# 23_LMS2_RX1_BB_ADC.net
KiCad netlist of a schematic drawn in Altium Designer
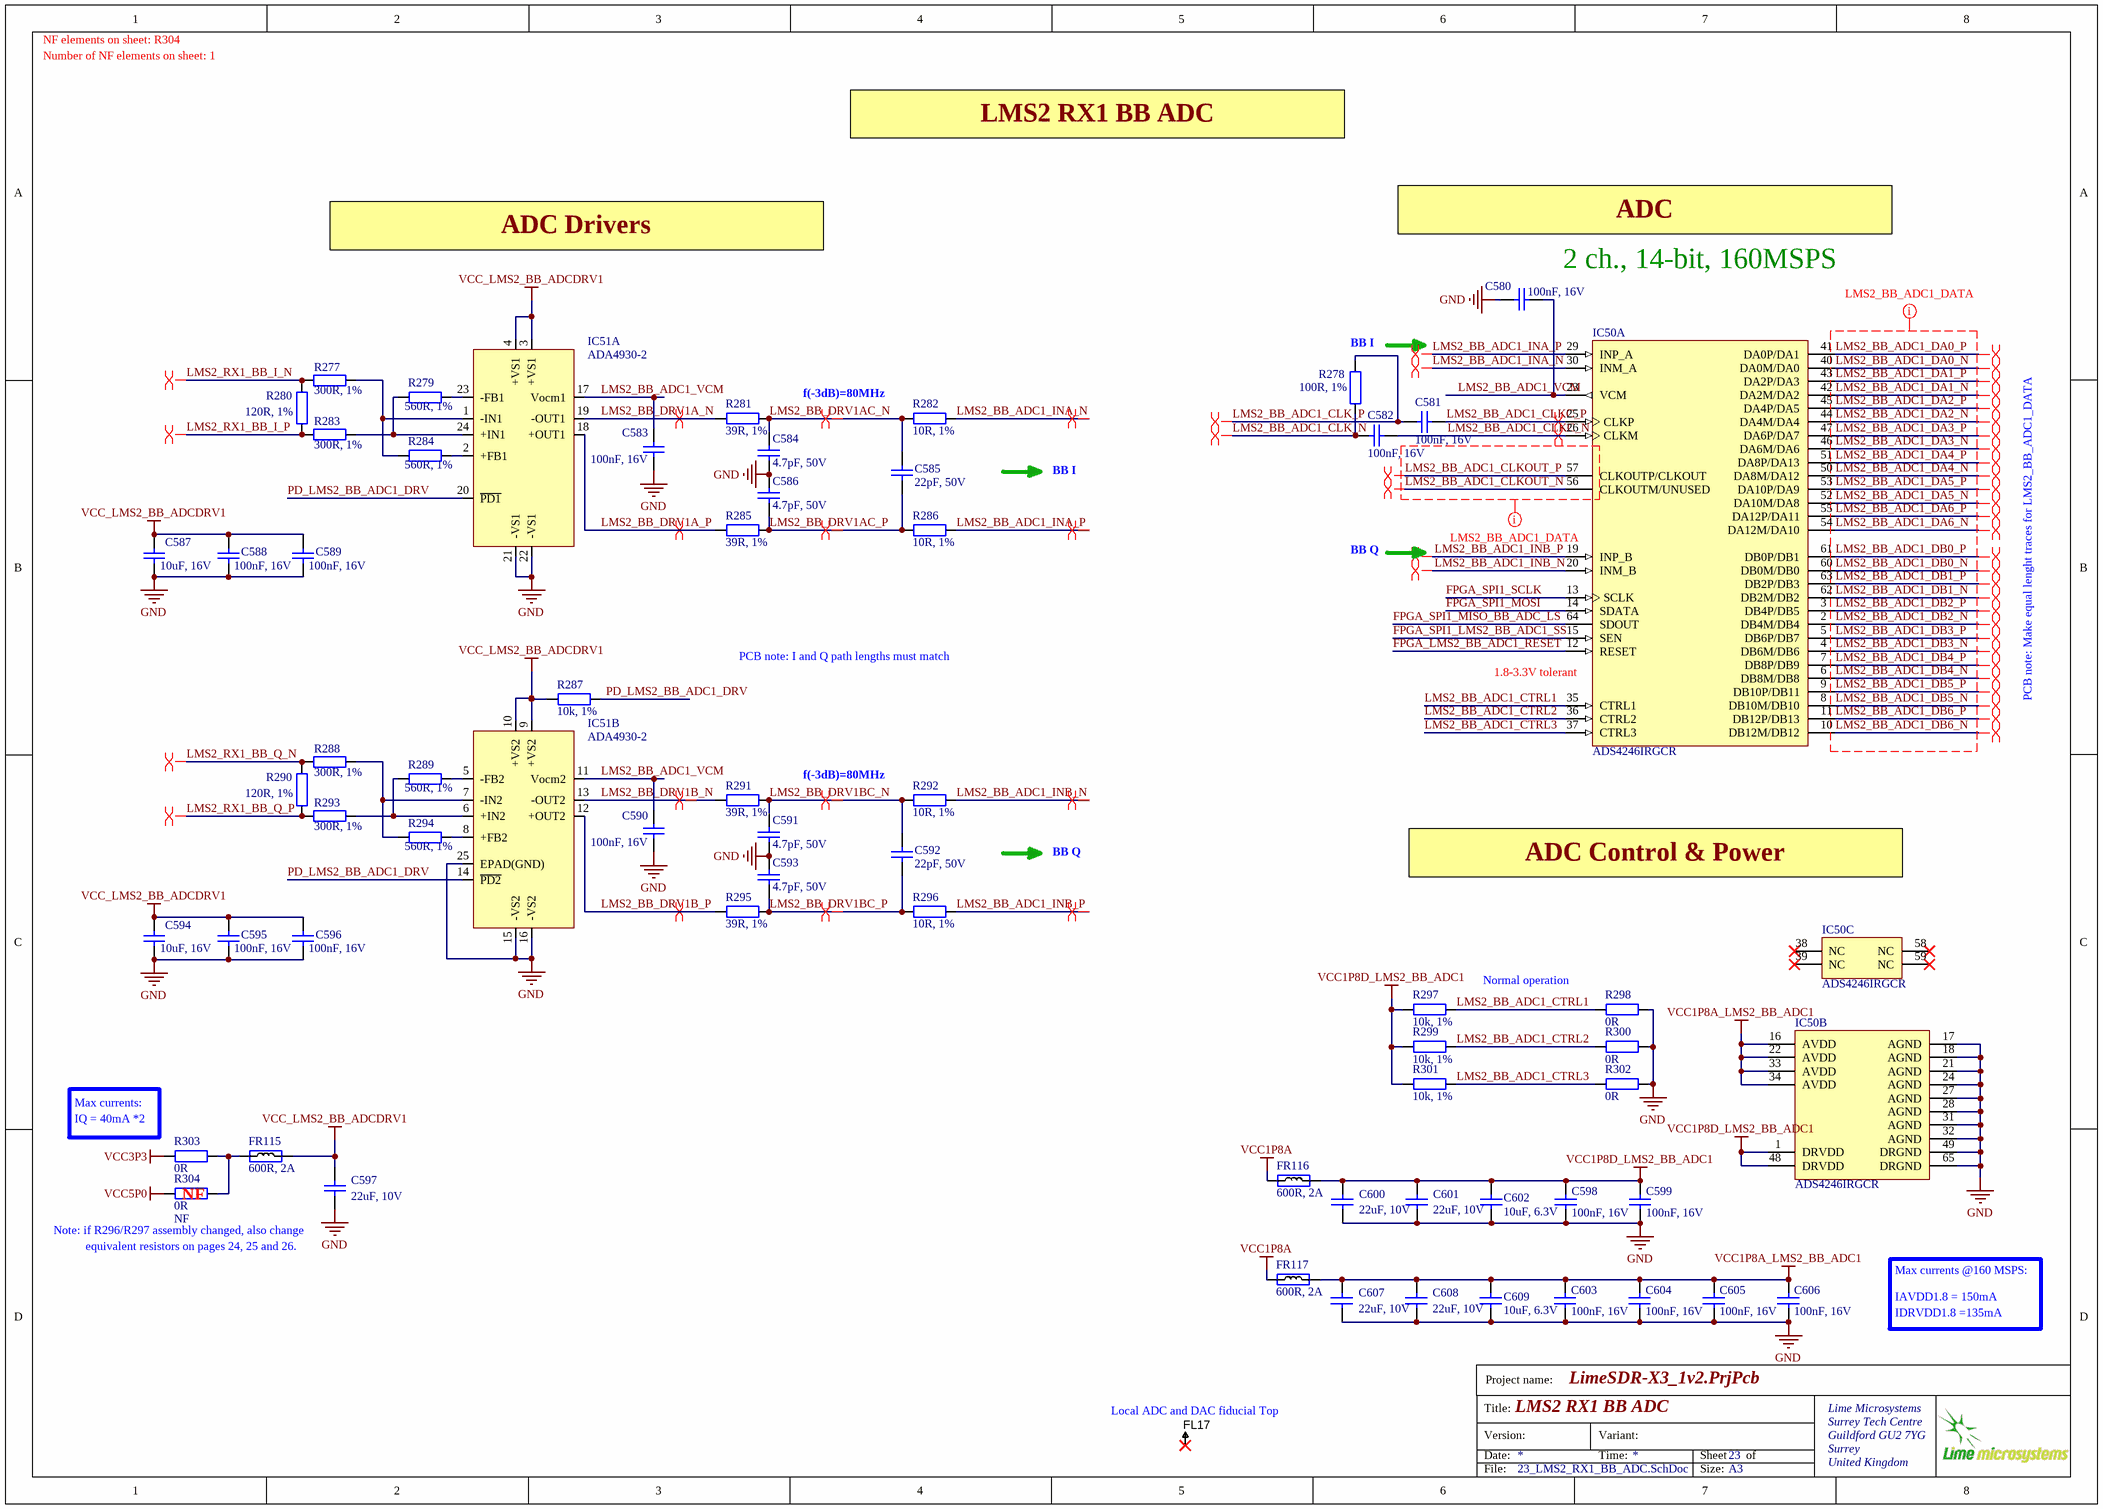
[diagram p0: 23_LMS2_RX1_BB_ADC.SchDoc]

(export (version "E")
  (design (tool "Eeschema 10.0.6"))
  (components
    (comp (ref "C580")
      (value "100nF, 16V")
      (footprint "CAP0402")
      (fields (field (name "TOLERANCE") "10 %") (field (name "MANUFACTURER") "Murata Electronics"))
      (libsource (lib "") (part "Cap_0603_1"))
    )
    (comp (ref "C581")
      (value "100nF, 16V")
      (footprint "CAP0402")
      (fields (field (name "TOLERANCE") "10 %") (field (name "MANUFACTURER") "Murata Electronics"))
      (libsource (lib "") (part "Cap_0603_1"))
    )
    (comp (ref "C582")
      (value "100nF, 16V")
      (footprint "CAP0402")
      (fields (field (name "TOLERANCE") "10 %") (field (name "MANUFACTURER") "Murata Electronics"))
      (libsource (lib "") (part "Cap_0603_2"))
    )
    (comp (ref "C583")
      (value "100nF, 16V")
      (footprint "CAP0402")
      (fields (field (name "TOLERANCE") "10 %") (field (name "MANUFACTURER") "Murata Electronics"))
      (libsource (lib "") (part "Cap_0603_2"))
    )
    (comp (ref "C584")
      (value "4.7pF, 50V")
      (footprint "CAP0402")
      (fields (field (name "MANUFACTURER") "MURATA"))
      (libsource (lib "LimeMicroAltiumLib_schLib") (part "Cap_0402"))
    )
    (comp (ref "C585")
      (value "22pF, 50V")
      (footprint "CAP0402")
      (fields (field (name "TOLERANCE") "±5%") (field (name "MANUFACTURER") "Yageo"))
      (libsource (lib "") (part "Cap_0402_1"))
    )
    (comp (ref "C586")
      (value "4.7pF, 50V")
      (footprint "CAP0402")
      (fields (field (name "MANUFACTURER") "MURATA"))
      (libsource (lib "LimeMicroAltiumLib_schLib") (part "Cap_0402"))
    )
    (comp (ref "C587")
      (value "10uF, 16V")
      (footprint "CAP0603")
      (fields (field (name "MANUFACTURER") "Yageo") (field (name "TOLERANCE") "±20%"))
      (libsource (lib "LimeMicroAltiumLib_schLib") (part "Cap_0603"))
    )
    (comp (ref "C588")
      (value "100nF, 16V")
      (footprint "CAP0402")
      (fields (field (name "TOLERANCE") "10 %") (field (name "MANUFACTURER") "Murata Electronics"))
      (libsource (lib "") (part "Cap_0603_2"))
    )
    (comp (ref "C589")
      (value "100nF, 16V")
      (footprint "CAP0402")
      (fields (field (name "TOLERANCE") "10 %") (field (name "MANUFACTURER") "Murata Electronics"))
      (libsource (lib "") (part "Cap_0603_2"))
    )
    (comp (ref "C590")
      (value "100nF, 16V")
      (footprint "CAP0402")
      (fields (field (name "TOLERANCE") "10 %") (field (name "MANUFACTURER") "Murata Electronics"))
      (libsource (lib "") (part "Cap_0603_5"))
    )
    (comp (ref "C591")
      (value "4.7pF, 50V")
      (footprint "CAP0402")
      (fields (field (name "MANUFACTURER") "MURATA"))
      (libsource (lib "LimeMicroAltiumLib_schLib") (part "Cap_0402"))
    )
    (comp (ref "C592")
      (value "22pF, 50V")
      (footprint "CAP0402")
      (fields (field (name "TOLERANCE") "±5%") (field (name "MANUFACTURER") "Yageo"))
      (libsource (lib "") (part "Cap_0402_1"))
    )
    (comp (ref "C593")
      (value "4.7pF, 50V")
      (footprint "CAP0402")
      (fields (field (name "MANUFACTURER") "MURATA"))
      (libsource (lib "LimeMicroAltiumLib_schLib") (part "Cap_0402"))
    )
    (comp (ref "C594")
      (value "10uF, 16V")
      (footprint "CAP0603")
      (fields (field (name "MANUFACTURER") "Yageo") (field (name "TOLERANCE") "±20%"))
      (libsource (lib "LimeMicroAltiumLib_schLib") (part "Cap_0603"))
    )
    (comp (ref "C595")
      (value "100nF, 16V")
      (footprint "CAP0402")
      (fields (field (name "TOLERANCE") "10 %") (field (name "MANUFACTURER") "Murata Electronics"))
      (libsource (lib "") (part "Cap_0603_2"))
    )
    (comp (ref "C596")
      (value "100nF, 16V")
      (footprint "CAP0402")
      (fields (field (name "TOLERANCE") "10 %") (field (name "MANUFACTURER") "Murata Electronics"))
      (libsource (lib "") (part "Cap_0603_2"))
    )
    (comp (ref "C597")
      (value "22uF, 10V")
      (footprint "CAP0603")
      (fields (field (name "TOLERANCE") "20 %") (field (name "MANUFACTURER") "TDK Corporation"))
      (libsource (lib "") (part "Cap_0603_4"))
    )
    (comp (ref "C598")
      (value "100nF, 16V")
      (footprint "CAP0402")
      (fields (field (name "TOLERANCE") "10 %") (field (name "MANUFACTURER") "Murata Electronics"))
      (libsource (lib "") (part "Cap_0603_3"))
    )
    (comp (ref "C599")
      (value "100nF, 16V")
      (footprint "CAP0402")
      (fields (field (name "TOLERANCE") "10 %") (field (name "MANUFACTURER") "Murata Electronics"))
      (libsource (lib "") (part "Cap_0603_3"))
    )
    (comp (ref "C600")
      (value "22uF, 10V")
      (footprint "CAP0603")
      (fields (field (name "TOLERANCE") "20 %") (field (name "MANUFACTURER") "TDK Corporation"))
      (libsource (lib "") (part "Cap_0603_3"))
    )
    (comp (ref "C601")
      (value "22uF, 10V")
      (footprint "CAP0603")
      (fields (field (name "TOLERANCE") "20 %") (field (name "MANUFACTURER") "TDK Corporation"))
      (libsource (lib "") (part "Cap_0603_3"))
    )
    (comp (ref "C602")
      (value "10uF, 6.3V")
      (footprint "CAP0603")
      (fields (field (name "TOLERANCE") "±20%") (field (name "MANUFACTURER") "Yageo"))
      (libsource (lib "") (part "Cap_0603_6"))
    )
    (comp (ref "C603")
      (value "100nF, 16V")
      (footprint "CAP0402")
      (fields (field (name "TOLERANCE") "10 %") (field (name "MANUFACTURER") "Murata Electronics"))
      (libsource (lib "LimeFPGAboard_schLib") (part "Cap_0603"))
    )
    (comp (ref "C604")
      (value "100nF, 16V")
      (footprint "CAP0402")
      (fields (field (name "TOLERANCE") "10 %") (field (name "MANUFACTURER") "Murata Electronics"))
      (libsource (lib "LimeFPGAboard_schLib") (part "Cap_0603"))
    )
    (comp (ref "C605")
      (value "100nF, 16V")
      (footprint "CAP0402")
      (fields (field (name "TOLERANCE") "10 %") (field (name "MANUFACTURER") "Murata Electronics"))
      (libsource (lib "LimeFPGAboard_schLib") (part "Cap_0603"))
    )
    (comp (ref "C606")
      (value "100nF, 16V")
      (footprint "CAP0402")
      (fields (field (name "TOLERANCE") "10 %") (field (name "MANUFACTURER") "Murata Electronics"))
      (libsource (lib "LimeFPGAboard_schLib") (part "Cap_0603"))
    )
    (comp (ref "C607")
      (value "22uF, 10V")
      (footprint "CAP0603")
      (fields (field (name "TOLERANCE") "20 %") (field (name "MANUFACTURER") "TDK Corporation"))
      (libsource (lib "LimeFPGAboard_schLib") (part "Cap_0603"))
    )
    (comp (ref "C608")
      (value "22uF, 10V")
      (footprint "CAP0603")
      (fields (field (name "TOLERANCE") "20 %") (field (name "MANUFACTURER") "TDK Corporation"))
      (libsource (lib "LimeFPGAboard_schLib") (part "Cap_0603"))
    )
    (comp (ref "C609")
      (value "10uF, 6.3V")
      (footprint "CAP0603")
      (fields (field (name "TOLERANCE") "±20%") (field (name "MANUFACTURER") "Yageo"))
      (libsource (lib "") (part "Cap_0603_7"))
    )
    (comp (ref "FL17")
      (value "Fiducial")
      (footprint "Fiducial_local")
      (libsource (lib "LimeMicroAltiumLib_schLib") (part "Fiducial"))
    )
    (comp (ref "FR115")
      (value "600R, 2A")
      (footprint "RES0805")
      (fields (field (name "MANUFACTURER") "TDK Corporation"))
      (libsource (lib "LimeMicroAltiumLib_schLib") (part "Ferrite"))
    )
    (comp (ref "FR116")
      (value "600R, 2A")
      (footprint "RES0805")
      (fields (field (name "MANUFACTURER") "TDK Corporation"))
      (libsource (lib "LimeFPGAboard_schLib") (part "Ferrite"))
    )
    (comp (ref "FR117")
      (value "600R, 2A")
      (footprint "RES0805")
      (fields (field (name "MANUFACTURER") "TDK Corporation"))
      (libsource (lib "LimeFPGAboard_schLib") (part "Ferrite"))
    )
    (comp (ref "IC50")
      (value "ADS4246IRGCR")
      (footprint "TI-RGC64-7400X7400TP_V")
      (description "14-Bit 160 MSPS Dual Low Power ADC, -40 to 85 degC, 64-pin QFN (RGC64), Green (RoHS & no Sb/Br)")
      (fields (field (name "MANUFACTURER") "Texas Instruments"))
      (libsource (lib "") (part "ADS4246IRGCR_1"))
    )
    (comp (ref "IC51")
      (value "ADA4930-2")
      (footprint "ADA4930-2_LFCSP-24")
      (fields (field (name "MANUFACTURER") "Analog Devices Inc."))
      (libsource (lib "") (part "ADA4930-2_1"))
    )
    (comp (ref "R277")
      (value "300R, 1%")
      (footprint "RES0402")
      (fields (field (name "TOLERANCE") "±1%") (field (name "MANUFACTURER") "Vishay Dale"))
      (libsource (lib "LimeFPGAboard_schLib") (part "Res_0402"))
    )
    (comp (ref "R278")
      (value "100R, 1%")
      (footprint "RES0402")
      (fields (field (name "TOLERANCE") "±1%") (field (name "MANUFACTURER") "Stackpole Electronics Inc."))
      (libsource (lib "LimeFPGAboard_schLib") (part "Res_0402"))
    )
    (comp (ref "R279")
      (value "560R, 1%")
      (footprint "RES0402")
      (fields (field (name "TOLERANCE") "±1%") (field (name "MANUFACTURER") "Vishay Dale"))
      (libsource (lib "LimeFPGAboard_schLib") (part "Res_0402"))
    )
    (comp (ref "R280")
      (value "120R, 1%")
      (footprint "RES0402")
      (fields (field (name "MANUFACTURER") "Yageo") (field (name "TOLERANCE") "1%"))
      (libsource (lib "") (part "Res_0402_1"))
    )
    (comp (ref "R281")
      (value "39R, 1%")
      (footprint "RES0402")
      (fields (field (name "MANUFACTURER") "Yageo") (field (name "TOLERANCE") "1%"))
      (libsource (lib "LimeMicroAltiumLib_schLib") (part "Res_0402"))
    )
    (comp (ref "R282")
      (value "10R, 1%")
      (footprint "RES0402")
      (fields (field (name "TOLERANCE") "1%"))
      (libsource (lib "LimeMicroAltiumLib_schLib") (part "Res_0402"))
    )
    (comp (ref "R283")
      (value "300R, 1%")
      (footprint "RES0402")
      (fields (field (name "TOLERANCE") "±1%") (field (name "MANUFACTURER") "Vishay Dale"))
      (libsource (lib "LimeFPGAboard_schLib") (part "Res_0402"))
    )
    (comp (ref "R284")
      (value "560R, 1%")
      (footprint "RES0402")
      (fields (field (name "TOLERANCE") "±1%") (field (name "MANUFACTURER") "Vishay Dale"))
      (libsource (lib "LimeFPGAboard_schLib") (part "Res_0402"))
    )
    (comp (ref "R285")
      (value "39R, 1%")
      (footprint "RES0402")
      (fields (field (name "MANUFACTURER") "Yageo") (field (name "TOLERANCE") "1%"))
      (libsource (lib "LimeMicroAltiumLib_schLib") (part "Res_0402"))
    )
    (comp (ref "R286")
      (value "10R, 1%")
      (footprint "RES0402")
      (fields (field (name "TOLERANCE") "1%"))
      (libsource (lib "LimeMicroAltiumLib_schLib") (part "Res_0402"))
    )
    (comp (ref "R287")
      (value "10k, 1%")
      (footprint "RES0402")
      (fields (field (name "MANUFACTURER") "Yageo") (field (name "TOLERANCE") "±1%"))
      (libsource (lib "LimeMicroAltiumLib_schLib") (part "Res_0402"))
    )
    (comp (ref "R288")
      (value "300R, 1%")
      (footprint "RES0402")
      (fields (field (name "TOLERANCE") "±1%") (field (name "MANUFACTURER") "Vishay Dale"))
      (libsource (lib "LimeFPGAboard_schLib") (part "Res_0402"))
    )
    (comp (ref "R289")
      (value "560R, 1%")
      (footprint "RES0402")
      (fields (field (name "TOLERANCE") "±1%") (field (name "MANUFACTURER") "Vishay Dale"))
      (libsource (lib "LimeFPGAboard_schLib") (part "Res_0402"))
    )
    (comp (ref "R290")
      (value "120R, 1%")
      (footprint "RES0402")
      (fields (field (name "MANUFACTURER") "Yageo") (field (name "TOLERANCE") "1%"))
      (libsource (lib "") (part "Res_0402_1"))
    )
    (comp (ref "R291")
      (value "39R, 1%")
      (footprint "RES0402")
      (fields (field (name "MANUFACTURER") "Yageo") (field (name "TOLERANCE") "1%"))
      (libsource (lib "LimeMicroAltiumLib_schLib") (part "Res_0402"))
    )
    (comp (ref "R292")
      (value "10R, 1%")
      (footprint "RES0402")
      (fields (field (name "TOLERANCE") "1%"))
      (libsource (lib "LimeMicroAltiumLib_schLib") (part "Res_0402"))
    )
    (comp (ref "R293")
      (value "300R, 1%")
      (footprint "RES0402")
      (fields (field (name "TOLERANCE") "±1%") (field (name "MANUFACTURER") "Vishay Dale"))
      (libsource (lib "LimeFPGAboard_schLib") (part "Res_0402"))
    )
    (comp (ref "R294")
      (value "560R, 1%")
      (footprint "RES0402")
      (fields (field (name "TOLERANCE") "±1%") (field (name "MANUFACTURER") "Vishay Dale"))
      (libsource (lib "LimeFPGAboard_schLib") (part "Res_0402"))
    )
    (comp (ref "R295")
      (value "39R, 1%")
      (footprint "RES0402")
      (fields (field (name "MANUFACTURER") "Yageo") (field (name "TOLERANCE") "1%"))
      (libsource (lib "LimeMicroAltiumLib_schLib") (part "Res_0402"))
    )
    (comp (ref "R296")
      (value "10R, 1%")
      (footprint "RES0402")
      (fields (field (name "TOLERANCE") "1%"))
      (libsource (lib "LimeMicroAltiumLib_schLib") (part "Res_0402"))
    )
    (comp (ref "R297")
      (value "10k, 1%")
      (footprint "RES0402")
      (fields (field (name "MANUFACTURER") "Yageo") (field (name "TOLERANCE") "±1%"))
      (libsource (lib "LimeMicroAltiumLib_schLib") (part "Res_0402"))
    )
    (comp (ref "R298")
      (value "0R")
      (footprint "RES0402")
      (fields (field (name "MANUFACTURER") "Yageo"))
      (libsource (lib "LimeFPGAboard_schLib") (part "Res_0402"))
    )
    (comp (ref "R299")
      (value "10k, 1%")
      (footprint "RES0402")
      (fields (field (name "MANUFACTURER") "Yageo") (field (name "TOLERANCE") "±1%"))
      (libsource (lib "LimeMicroAltiumLib_schLib") (part "Res_0402"))
    )
    (comp (ref "R300")
      (value "0R")
      (footprint "RES0402")
      (fields (field (name "MANUFACTURER") "Yageo"))
      (libsource (lib "LimeFPGAboard_schLib") (part "Res_0402"))
    )
    (comp (ref "R301")
      (value "10k, 1%")
      (footprint "RES0402")
      (fields (field (name "MANUFACTURER") "Yageo") (field (name "TOLERANCE") "±1%"))
      (libsource (lib "LimeMicroAltiumLib_schLib") (part "Res_0402"))
    )
    (comp (ref "R302")
      (value "0R")
      (footprint "RES0402")
      (fields (field (name "MANUFACTURER") "Yageo"))
      (libsource (lib "LimeFPGAboard_schLib") (part "Res_0402"))
    )
    (comp (ref "R303")
      (value "0R")
      (footprint "RES0402")
      (fields (field (name "MANUFACTURER") "Yageo") (field (name "TOLERANCE") "Jumper"))
      (libsource (lib "LimeMicroAltiumLib_schLib") (part "Res_0402"))
    )
    (comp (ref "R304")
      (value "0R")
      (footprint "RES0402")
      (fields
        (field (name "ASSEMBLY INFO") "NF")
        (field (name "MANUFACTURER") "Yageo")
        (field (name "TOLERANCE") "Jumper")
      )
      (libsource (lib "LimeMicroAltiumLib_schLib") (part "Res_0402"))
    )
  )
  (nets
    (net (code "1") (name "/FPGA_LMS2_BB_ADC1_RESET") (class "Default")
      (node (ref "IC50") (pin "12") (pinfunction "RESET_12") (pintype "input"))
    )
    (net (code "2") (name "/FPGA_SPI1_LMS2_BB_ADC1_SS") (class "Default")
      (node (ref "IC50") (pin "15") (pinfunction "SEN_15") (pintype "input"))
    )
    (net (code "3") (name "/FPGA_SPI1_MISO_BB_ADC_LS") (class "Default")
      (node (ref "IC50") (pin "64") (pinfunction "SDOUT_64") (pintype "tri_state"))
    )
    (net (code "4") (name "/FPGA_SPI1_MOSI") (class "Default")
      (node (ref "IC50") (pin "14") (pinfunction "SDATA_14") (pintype "input"))
    )
    (net (code "5") (name "/FPGA_SPI1_SCLK") (class "Default")
      (node (ref "IC50") (pin "13") (pinfunction "SCLK_13") (pintype "input"))
    )
    (net (code "6") (name "/LMS2_BB_ADC1_CLKC_N") (class "Default")
      (node (ref "C582") (pin "1") (pinfunction "1_1") (pintype "passive"))
      (node (ref "IC50") (pin "26") (pinfunction "CLKM_26") (pintype "input"))
    )
    (net (code "7") (name "/LMS2_BB_ADC1_CLKC_P") (class "Default")
      (node (ref "C581") (pin "1") (pinfunction "1_1") (pintype "passive"))
      (node (ref "IC50") (pin "25") (pinfunction "CLKP_25") (pintype "input"))
    )
    (net (code "8") (name "/LMS2_BB_ADC1_CLKOUT_N") (class "Default")
      (node (ref "IC50") (pin "56") (pinfunction "CLKOUTM/UNUSED_56") (pintype "tri_state"))
    )
    (net (code "9") (name "/LMS2_BB_ADC1_CLKOUT_P") (class "Default")
      (node (ref "IC50") (pin "57") (pinfunction "CLKOUTP/CLKOUT_57") (pintype "tri_state"))
    )
    (net (code "10") (name "/LMS2_BB_ADC1_CLK_N") (class "Default")
      (node (ref "C582") (pin "2") (pinfunction "2_2") (pintype "passive"))
      (node (ref "R278") (pin "1") (pinfunction "1_1") (pintype "passive"))
    )
    (net (code "11") (name "/LMS2_BB_ADC1_CLK_P") (class "Default")
      (node (ref "C581") (pin "2") (pinfunction "2_2") (pintype "passive"))
      (node (ref "R278") (pin "2") (pinfunction "2_2") (pintype "passive"))
    )
    (net (code "12") (name "/LMS2_BB_ADC1_CTRL1") (class "Default")
      (node (ref "IC50") (pin "35") (pinfunction "CTRL1_35") (pintype "input"))
      (node (ref "R297") (pin "1") (pinfunction "1_1") (pintype "passive"))
      (node (ref "R298") (pin "2") (pinfunction "2_2") (pintype "passive"))
    )
    (net (code "13") (name "/LMS2_BB_ADC1_CTRL2") (class "Default")
      (node (ref "IC50") (pin "36") (pinfunction "CTRL2_36") (pintype "input"))
      (node (ref "R299") (pin "1") (pinfunction "1_1") (pintype "passive"))
      (node (ref "R300") (pin "2") (pinfunction "2_2") (pintype "passive"))
    )
    (net (code "14") (name "/LMS2_BB_ADC1_CTRL3") (class "Default")
      (node (ref "IC50") (pin "37") (pinfunction "CTRL3_37") (pintype "input"))
      (node (ref "R301") (pin "1") (pinfunction "1_1") (pintype "passive"))
      (node (ref "R302") (pin "2") (pinfunction "2_2") (pintype "passive"))
    )
    (net (code "15") (name "/LMS2_BB_ADC1_DA0_N") (class "Default")
      (node (ref "IC50") (pin "40") (pinfunction "DA0M/DA0_40") (pintype "tri_state"))
    )
    (net (code "16") (name "/LMS2_BB_ADC1_DA0_P") (class "Default")
      (node (ref "IC50") (pin "41") (pinfunction "DA0P/DA1_41") (pintype "tri_state"))
    )
    (net (code "17") (name "/LMS2_BB_ADC1_DA1_N") (class "Default")
      (node (ref "IC50") (pin "42") (pinfunction "DA2M/DA2_42") (pintype "tri_state"))
    )
    (net (code "18") (name "/LMS2_BB_ADC1_DA1_P") (class "Default")
      (node (ref "IC50") (pin "43") (pinfunction "DA2P/DA3_43") (pintype "tri_state"))
    )
    (net (code "19") (name "/LMS2_BB_ADC1_DA2_N") (class "Default")
      (node (ref "IC50") (pin "44") (pinfunction "DA4M/DA4_44") (pintype "tri_state"))
    )
    (net (code "20") (name "/LMS2_BB_ADC1_DA2_P") (class "Default")
      (node (ref "IC50") (pin "45") (pinfunction "DA4P/DA5_45") (pintype "tri_state"))
    )
    (net (code "21") (name "/LMS2_BB_ADC1_DA3_N") (class "Default")
      (node (ref "IC50") (pin "46") (pinfunction "DA6M/DA6_46") (pintype "tri_state"))
    )
    (net (code "22") (name "/LMS2_BB_ADC1_DA3_P") (class "Default")
      (node (ref "IC50") (pin "47") (pinfunction "DA6P/DA7_47") (pintype "tri_state"))
    )
    (net (code "23") (name "/LMS2_BB_ADC1_DA4_N") (class "Default")
      (node (ref "IC50") (pin "50") (pinfunction "DA8M/DA12_50") (pintype "tri_state"))
    )
    (net (code "24") (name "/LMS2_BB_ADC1_DA4_P") (class "Default")
      (node (ref "IC50") (pin "51") (pinfunction "DA8P/DA13_51") (pintype "tri_state"))
    )
    (net (code "25") (name "/LMS2_BB_ADC1_DA5_N") (class "Default")
      (node (ref "IC50") (pin "52") (pinfunction "DA10M/DA8_52") (pintype "tri_state"))
    )
    (net (code "26") (name "/LMS2_BB_ADC1_DA5_P") (class "Default")
      (node (ref "IC50") (pin "53") (pinfunction "DA10P/DA9_53") (pintype "tri_state"))
    )
    (net (code "27") (name "/LMS2_BB_ADC1_DA6_N") (class "Default")
      (node (ref "IC50") (pin "54") (pinfunction "DA12M/DA10_54") (pintype "tri_state"))
    )
    (net (code "28") (name "/LMS2_BB_ADC1_DA6_P") (class "Default")
      (node (ref "IC50") (pin "55") (pinfunction "DA12P/DA11_55") (pintype "tri_state"))
    )
    (net (code "29") (name "/LMS2_BB_ADC1_DB0_N") (class "Default")
      (node (ref "IC50") (pin "60") (pinfunction "DB0M/DB0_60") (pintype "tri_state"))
    )
    (net (code "30") (name "/LMS2_BB_ADC1_DB0_P") (class "Default")
      (node (ref "IC50") (pin "61") (pinfunction "DB0P/DB1_61") (pintype "tri_state"))
    )
    (net (code "31") (name "/LMS2_BB_ADC1_DB1_N") (class "Default")
      (node (ref "IC50") (pin "62") (pinfunction "DB2M/DB2_62") (pintype "tri_state"))
    )
    (net (code "32") (name "/LMS2_BB_ADC1_DB1_P") (class "Default")
      (node (ref "IC50") (pin "63") (pinfunction "DB2P/DB3_63") (pintype "tri_state"))
    )
    (net (code "33") (name "/LMS2_BB_ADC1_DB2_N") (class "Default")
      (node (ref "IC50") (pin "2") (pinfunction "DB4M/DB4_2") (pintype "tri_state"))
    )
    (net (code "34") (name "/LMS2_BB_ADC1_DB2_P") (class "Default")
      (node (ref "IC50") (pin "3") (pinfunction "DB4P/DB5_3") (pintype "tri_state"))
    )
    (net (code "35") (name "/LMS2_BB_ADC1_DB3_N") (class "Default")
      (node (ref "IC50") (pin "4") (pinfunction "DB6M/DB6_4") (pintype "tri_state"))
    )
    (net (code "36") (name "/LMS2_BB_ADC1_DB3_P") (class "Default")
      (node (ref "IC50") (pin "5") (pinfunction "DB6P/DB7_5") (pintype "tri_state"))
    )
    (net (code "37") (name "/LMS2_BB_ADC1_DB4_N") (class "Default")
      (node (ref "IC50") (pin "6") (pinfunction "DB8M/DB8_6") (pintype "tri_state"))
    )
    (net (code "38") (name "/LMS2_BB_ADC1_DB4_P") (class "Default")
      (node (ref "IC50") (pin "7") (pinfunction "DB8P/DB9_7") (pintype "tri_state"))
    )
    (net (code "39") (name "/LMS2_BB_ADC1_DB5_N") (class "Default")
      (node (ref "IC50") (pin "8") (pinfunction "DB10M/DB10_8") (pintype "tri_state"))
    )
    (net (code "40") (name "/LMS2_BB_ADC1_DB5_P") (class "Default")
      (node (ref "IC50") (pin "9") (pinfunction "DB10P/DB11_9") (pintype "tri_state"))
    )
    (net (code "41") (name "/LMS2_BB_ADC1_DB6_N") (class "Default")
      (node (ref "IC50") (pin "10") (pinfunction "DB12M/DB12_10") (pintype "tri_state"))
    )
    (net (code "42") (name "/LMS2_BB_ADC1_DB6_P") (class "Default")
      (node (ref "IC50") (pin "11") (pinfunction "DB12P/DB13_11") (pintype "tri_state"))
    )
    (net (code "43") (name "/LMS2_BB_ADC1_INA_N") (class "Default")
      (node (ref "IC50") (pin "30") (pinfunction "INM_A_30") (pintype "input"))
      (node (ref "R282") (pin "1") (pinfunction "1_1") (pintype "passive"))
    )
    (net (code "44") (name "/LMS2_BB_ADC1_INA_P") (class "Default")
      (node (ref "IC50") (pin "29") (pinfunction "INP_A_29") (pintype "input"))
      (node (ref "R286") (pin "1") (pinfunction "1_1") (pintype "passive"))
    )
    (net (code "45") (name "/LMS2_BB_ADC1_INB_N") (class "Default")
      (node (ref "IC50") (pin "20") (pinfunction "INM_B_20") (pintype "input"))
      (node (ref "R292") (pin "1") (pinfunction "1_1") (pintype "passive"))
    )
    (net (code "46") (name "/LMS2_BB_ADC1_INB_P") (class "Default")
      (node (ref "IC50") (pin "19") (pinfunction "INP_B_19") (pintype "input"))
      (node (ref "R296") (pin "1") (pinfunction "1_1") (pintype "passive"))
    )
    (net (code "47") (name "/LMS2_BB_ADC1_VCM") (class "Default")
      (node (ref "C580") (pin "2") (pinfunction "2_2") (pintype "passive"))
      (node (ref "C583") (pin "1") (pinfunction "1_1") (pintype "passive"))
      (node (ref "C590") (pin "1") (pinfunction "1_1") (pintype "passive"))
      (node (ref "IC50") (pin "23") (pinfunction "VCM_23") (pintype "output"))
      (node (ref "IC51") (pin "11") (pinfunction "Vocm2_11") (pintype "input"))
      (node (ref "IC51") (pin "17") (pinfunction "Vocm1_17") (pintype "input"))
    )
    (net (code "48") (name "/LMS2_BB_DRV1AC_N") (class "Default")
      (node (ref "C584") (pin "1") (pinfunction "1_1") (pintype "passive"))
      (node (ref "C585") (pin "1") (pinfunction "1_1") (pintype "passive"))
      (node (ref "R281") (pin "1") (pinfunction "1_1") (pintype "passive"))
      (node (ref "R282") (pin "2") (pinfunction "2_2") (pintype "passive"))
    )
    (net (code "49") (name "/LMS2_BB_DRV1AC_P") (class "Default")
      (node (ref "C585") (pin "2") (pinfunction "2_2") (pintype "passive"))
      (node (ref "C586") (pin "2") (pinfunction "2_2") (pintype "passive"))
      (node (ref "R285") (pin "1") (pinfunction "1_1") (pintype "passive"))
      (node (ref "R286") (pin "2") (pinfunction "2_2") (pintype "passive"))
    )
    (net (code "50") (name "/LMS2_BB_DRV1A_N") (class "Default")
      (node (ref "IC51") (pin "19") (pinfunction "-OUT1_19") (pintype "output"))
      (node (ref "R281") (pin "2") (pinfunction "2_2") (pintype "passive"))
    )
    (net (code "51") (name "/LMS2_BB_DRV1A_P") (class "Default")
      (node (ref "IC51") (pin "18") (pinfunction "+OUT1_18") (pintype "output"))
      (node (ref "R285") (pin "2") (pinfunction "2_2") (pintype "passive"))
    )
    (net (code "52") (name "/LMS2_BB_DRV1BC_N") (class "Default")
      (node (ref "C591") (pin "1") (pinfunction "1_1") (pintype "passive"))
      (node (ref "C592") (pin "1") (pinfunction "1_1") (pintype "passive"))
      (node (ref "R291") (pin "1") (pinfunction "1_1") (pintype "passive"))
      (node (ref "R292") (pin "2") (pinfunction "2_2") (pintype "passive"))
    )
    (net (code "53") (name "/LMS2_BB_DRV1BC_P") (class "Default")
      (node (ref "C592") (pin "2") (pinfunction "2_2") (pintype "passive"))
      (node (ref "C593") (pin "2") (pinfunction "2_2") (pintype "passive"))
      (node (ref "R295") (pin "1") (pinfunction "1_1") (pintype "passive"))
      (node (ref "R296") (pin "2") (pinfunction "2_2") (pintype "passive"))
    )
    (net (code "54") (name "/LMS2_BB_DRV1B_N") (class "Default")
      (node (ref "IC51") (pin "13") (pinfunction "-OUT2_13") (pintype "output"))
      (node (ref "R291") (pin "2") (pinfunction "2_2") (pintype "passive"))
    )
    (net (code "55") (name "/LMS2_BB_DRV1B_P") (class "Default")
      (node (ref "IC51") (pin "12") (pinfunction "+OUT2_12") (pintype "output"))
      (node (ref "R295") (pin "2") (pinfunction "2_2") (pintype "passive"))
    )
    (net (code "56") (name "/LMS2_RX1_BB_I_N") (class "Default")
      (node (ref "R277") (pin "2") (pinfunction "2_2") (pintype "passive"))
      (node (ref "R280") (pin "2") (pinfunction "2_2") (pintype "passive"))
    )
    (net (code "57") (name "/LMS2_RX1_BB_I_P") (class "Default")
      (node (ref "R280") (pin "1") (pinfunction "1_1") (pintype "passive"))
      (node (ref "R283") (pin "2") (pinfunction "2_2") (pintype "passive"))
    )
    (net (code "58") (name "/LMS2_RX1_BB_Q_N") (class "Default")
      (node (ref "R288") (pin "2") (pinfunction "2_2") (pintype "passive"))
      (node (ref "R290") (pin "2") (pinfunction "2_2") (pintype "passive"))
    )
    (net (code "59") (name "/LMS2_RX1_BB_Q_P") (class "Default")
      (node (ref "R290") (pin "1") (pinfunction "1_1") (pintype "passive"))
      (node (ref "R293") (pin "2") (pinfunction "2_2") (pintype "passive"))
    )
    (net (code "60") (name "/PD_LMS2_BB_ADC1_DRV") (class "Default")
      (node (ref "IC51") (pin "14") (pinfunction "~{PD2}_14") (pintype "input"))
      (node (ref "IC51") (pin "20") (pinfunction "~{PD1}_20") (pintype "input"))
      (node (ref "R287") (pin "1") (pinfunction "1_1") (pintype "passive"))
    )
    (net (code "61") (name "GND") (class "Default")
      (node (ref "C580") (pin "1") (pinfunction "1_1") (pintype "passive"))
      (node (ref "C583") (pin "2") (pinfunction "2_2") (pintype "passive"))
      (node (ref "C584") (pin "2") (pinfunction "2_2") (pintype "passive"))
      (node (ref "C586") (pin "1") (pinfunction "1_1") (pintype "passive"))
      (node (ref "C587") (pin "1") (pinfunction "1_1") (pintype "passive"))
      (node (ref "C588") (pin "2") (pinfunction "2_2") (pintype "passive"))
      (node (ref "C589") (pin "2") (pinfunction "2_2") (pintype "passive"))
      (node (ref "C590") (pin "2") (pinfunction "2_2") (pintype "passive"))
      (node (ref "C591") (pin "2") (pinfunction "2_2") (pintype "passive"))
      (node (ref "C593") (pin "1") (pinfunction "1_1") (pintype "passive"))
      (node (ref "C594") (pin "1") (pinfunction "1_1") (pintype "passive"))
      (node (ref "C595") (pin "2") (pinfunction "2_2") (pintype "passive"))
      (node (ref "C596") (pin "2") (pinfunction "2_2") (pintype "passive"))
      (node (ref "C597") (pin "1") (pinfunction "1_1") (pintype "passive"))
      (node (ref "C598") (pin "1") (pinfunction "1_1") (pintype "passive"))
      (node (ref "C599") (pin "1") (pinfunction "1_1") (pintype "passive"))
      (node (ref "C600") (pin "1") (pinfunction "1_1") (pintype "passive"))
      (node (ref "C601") (pin "1") (pinfunction "1_1") (pintype "passive"))
      (node (ref "C602") (pin "2") (pinfunction "2_2") (pintype "passive"))
      (node (ref "C603") (pin "1") (pinfunction "1_1") (pintype "passive"))
      (node (ref "C604") (pin "1") (pinfunction "1_1") (pintype "passive"))
      (node (ref "C605") (pin "1") (pinfunction "1_1") (pintype "passive"))
      (node (ref "C606") (pin "1") (pinfunction "1_1") (pintype "passive"))
      (node (ref "C607") (pin "1") (pinfunction "1_1") (pintype "passive"))
      (node (ref "C608") (pin "1") (pinfunction "1_1") (pintype "passive"))
      (node (ref "C609") (pin "2") (pinfunction "2_2") (pintype "passive"))
      (node (ref "IC50") (pin "17") (pinfunction "AGND_17") (pintype "power_in"))
      (node (ref "IC50") (pin "18") (pinfunction "AGND_18") (pintype "power_in"))
      (node (ref "IC50") (pin "21") (pinfunction "AGND_21") (pintype "power_in"))
      (node (ref "IC50") (pin "24") (pinfunction "AGND_24") (pintype "power_in"))
      (node (ref "IC50") (pin "27") (pinfunction "AGND_27") (pintype "power_in"))
      (node (ref "IC50") (pin "28") (pinfunction "AGND_28") (pintype "power_in"))
      (node (ref "IC50") (pin "31") (pinfunction "AGND_31") (pintype "power_in"))
      (node (ref "IC50") (pin "32") (pinfunction "AGND_32") (pintype "power_in"))
      (node (ref "IC50") (pin "49") (pinfunction "DRGND_49") (pintype "power_in"))
      (node (ref "IC50") (pin "65") (pinfunction "DRGND_65") (pintype "power_in"))
      (node (ref "IC51") (pin "15") (pinfunction "-VS2_15") (pintype "power_in"))
      (node (ref "IC51") (pin "16") (pinfunction "-VS2_16") (pintype "power_in"))
      (node (ref "IC51") (pin "21") (pinfunction "-VS1_21") (pintype "power_in"))
      (node (ref "IC51") (pin "22") (pinfunction "-VS1_22") (pintype "power_in"))
      (node (ref "IC51") (pin "25") (pinfunction "EPAD(GND)_25") (pintype "passive"))
      (node (ref "R298") (pin "1") (pinfunction "1_1") (pintype "passive"))
      (node (ref "R300") (pin "1") (pinfunction "1_1") (pintype "passive"))
      (node (ref "R302") (pin "1") (pinfunction "1_1") (pintype "passive"))
    )
    (net (code "62") (name "Net-(FR115-Pad1)") (class "Default")
      (node (ref "FR115") (pin "1") (pinfunction "1_1") (pintype "passive"))
      (node (ref "R303") (pin "1") (pinfunction "1_1") (pintype "passive"))
      (node (ref "R304") (pin "1") (pinfunction "1_1") (pintype "passive"))
    )
    (net (code "63") (name "Net-(IC51A-+FB1)") (class "Default")
      (node (ref "IC51") (pin "2") (pinfunction "+FB1_2") (pintype "output"))
      (node (ref "R284") (pin "1") (pinfunction "1_1") (pintype "passive"))
    )
    (net (code "64") (name "Net-(IC51A-+IN1)") (class "Default")
      (node (ref "IC51") (pin "24") (pinfunction "+IN1_24") (pintype "input"))
      (node (ref "R279") (pin "2") (pinfunction "2_2") (pintype "passive"))
      (node (ref "R283") (pin "1") (pinfunction "1_1") (pintype "passive"))
    )
    (net (code "65") (name "Net-(IC51A--FB1)") (class "Default")
      (node (ref "IC51") (pin "23") (pinfunction "-FB1_23") (pintype "output"))
      (node (ref "R279") (pin "1") (pinfunction "1_1") (pintype "passive"))
    )
    (net (code "66") (name "Net-(IC51A--IN1)") (class "Default")
      (node (ref "IC51") (pin "1") (pinfunction "-IN1_1") (pintype "input"))
      (node (ref "R277") (pin "1") (pinfunction "1_1") (pintype "passive"))
      (node (ref "R284") (pin "2") (pinfunction "2_2") (pintype "passive"))
    )
    (net (code "67") (name "Net-(IC51B-+FB2)") (class "Default")
      (node (ref "IC51") (pin "8") (pinfunction "+FB2_8") (pintype "output"))
      (node (ref "R294") (pin "1") (pinfunction "1_1") (pintype "passive"))
    )
    (net (code "68") (name "Net-(IC51B-+IN2)") (class "Default")
      (node (ref "IC51") (pin "6") (pinfunction "+IN2_6") (pintype "input"))
      (node (ref "R289") (pin "2") (pinfunction "2_2") (pintype "passive"))
      (node (ref "R293") (pin "1") (pinfunction "1_1") (pintype "passive"))
    )
    (net (code "69") (name "Net-(IC51B--FB2)") (class "Default")
      (node (ref "IC51") (pin "5") (pinfunction "-FB2_5") (pintype "output"))
      (node (ref "R289") (pin "1") (pinfunction "1_1") (pintype "passive"))
    )
    (net (code "70") (name "Net-(IC51B--IN2)") (class "Default")
      (node (ref "IC51") (pin "7") (pinfunction "-IN2_7") (pintype "input"))
      (node (ref "R288") (pin "1") (pinfunction "1_1") (pintype "passive"))
      (node (ref "R294") (pin "2") (pinfunction "2_2") (pintype "passive"))
    )
    (net (code "71") (name "VCC1P8A") (class "Default")
      (node (ref "FR116") (pin "1") (pinfunction "1_1") (pintype "passive"))
      (node (ref "FR117") (pin "1") (pinfunction "1_1") (pintype "passive"))
    )
    (net (code "72") (name "VCC1P8A_LMS2_BB_ADC1") (class "Default")
      (node (ref "C603") (pin "2") (pinfunction "2_2") (pintype "passive"))
      (node (ref "C604") (pin "2") (pinfunction "2_2") (pintype "passive"))
      (node (ref "C605") (pin "2") (pinfunction "2_2") (pintype "passive"))
      (node (ref "C606") (pin "2") (pinfunction "2_2") (pintype "passive"))
      (node (ref "C607") (pin "2") (pinfunction "2_2") (pintype "passive"))
      (node (ref "C608") (pin "2") (pinfunction "2_2") (pintype "passive"))
      (node (ref "C609") (pin "1") (pinfunction "1_1") (pintype "passive"))
      (node (ref "FR117") (pin "2") (pinfunction "2_2") (pintype "passive"))
      (node (ref "IC50") (pin "16") (pinfunction "AVDD_16") (pintype "power_in"))
      (node (ref "IC50") (pin "22") (pinfunction "AVDD_22") (pintype "power_in"))
      (node (ref "IC50") (pin "33") (pinfunction "AVDD_33") (pintype "power_in"))
      (node (ref "IC50") (pin "34") (pinfunction "AVDD_34") (pintype "power_in"))
    )
    (net (code "73") (name "VCC1P8D_LMS2_BB_ADC1") (class "Default")
      (node (ref "C598") (pin "2") (pinfunction "2_2") (pintype "passive"))
      (node (ref "C599") (pin "2") (pinfunction "2_2") (pintype "passive"))
      (node (ref "C600") (pin "2") (pinfunction "2_2") (pintype "passive"))
      (node (ref "C601") (pin "2") (pinfunction "2_2") (pintype "passive"))
      (node (ref "C602") (pin "1") (pinfunction "1_1") (pintype "passive"))
      (node (ref "FR116") (pin "2") (pinfunction "2_2") (pintype "passive"))
      (node (ref "IC50") (pin "1") (pinfunction "DRVDD_1") (pintype "power_in"))
      (node (ref "IC50") (pin "48") (pinfunction "DRVDD_48") (pintype "power_in"))
      (node (ref "R297") (pin "2") (pinfunction "2_2") (pintype "passive"))
      (node (ref "R299") (pin "2") (pinfunction "2_2") (pintype "passive"))
      (node (ref "R301") (pin "2") (pinfunction "2_2") (pintype "passive"))
    )
    (net (code "74") (name "VCC3P3") (class "Default")
      (node (ref "R303") (pin "2") (pinfunction "2_2") (pintype "passive"))
    )
    (net (code "75") (name "VCC5P0") (class "Default")
      (node (ref "R304") (pin "2") (pinfunction "2_2") (pintype "passive"))
    )
    (net (code "76") (name "VCC_LMS2_BB_ADCDRV1") (class "Default")
      (node (ref "C587") (pin "2") (pinfunction "2_2") (pintype "passive"))
      (node (ref "C588") (pin "1") (pinfunction "1_1") (pintype "passive"))
      (node (ref "C589") (pin "1") (pinfunction "1_1") (pintype "passive"))
      (node (ref "C594") (pin "2") (pinfunction "2_2") (pintype "passive"))
      (node (ref "C595") (pin "1") (pinfunction "1_1") (pintype "passive"))
      (node (ref "C596") (pin "1") (pinfunction "1_1") (pintype "passive"))
      (node (ref "C597") (pin "2") (pinfunction "2_2") (pintype "passive"))
      (node (ref "FR115") (pin "2") (pinfunction "2_2") (pintype "passive"))
      (node (ref "IC51") (pin "10") (pinfunction "+VS2_10") (pintype "power_in"))
      (node (ref "IC51") (pin "3") (pinfunction "+VS1_3") (pintype "power_in"))
      (node (ref "IC51") (pin "4") (pinfunction "+VS1_4") (pintype "power_in"))
      (node (ref "IC51") (pin "9") (pinfunction "+VS2_9") (pintype "power_in"))
      (node (ref "R287") (pin "2") (pinfunction "2_2") (pintype "passive"))
    )
    (net (code "77") (name "unconnected-(FL17-Pad1)") (class "Default")
      (node (ref "FL17") (pin "1") (pintype "passive+no_connect"))
    )
    (net (code "78") (name "unconnected-(IC50C-NC-Pad38)") (class "Default")
      (node (ref "IC50") (pin "38") (pinfunction "NC_38") (pintype "passive+no_connect"))
    )
    (net (code "79") (name "unconnected-(IC50C-NC-Pad39)") (class "Default")
      (node (ref "IC50") (pin "39") (pinfunction "NC_39") (pintype "passive+no_connect"))
    )
    (net (code "80") (name "unconnected-(IC50C-NC-Pad58)") (class "Default")
      (node (ref "IC50") (pin "58") (pinfunction "NC_58") (pintype "passive+no_connect"))
    )
    (net (code "81") (name "unconnected-(IC50C-NC-Pad59)") (class "Default")
      (node (ref "IC50") (pin "59") (pinfunction "NC_59") (pintype "passive+no_connect"))
    )
  )
)
